# arduinoDcc1_2.net
KiCad netlist of a schematic drawn in EAGLE
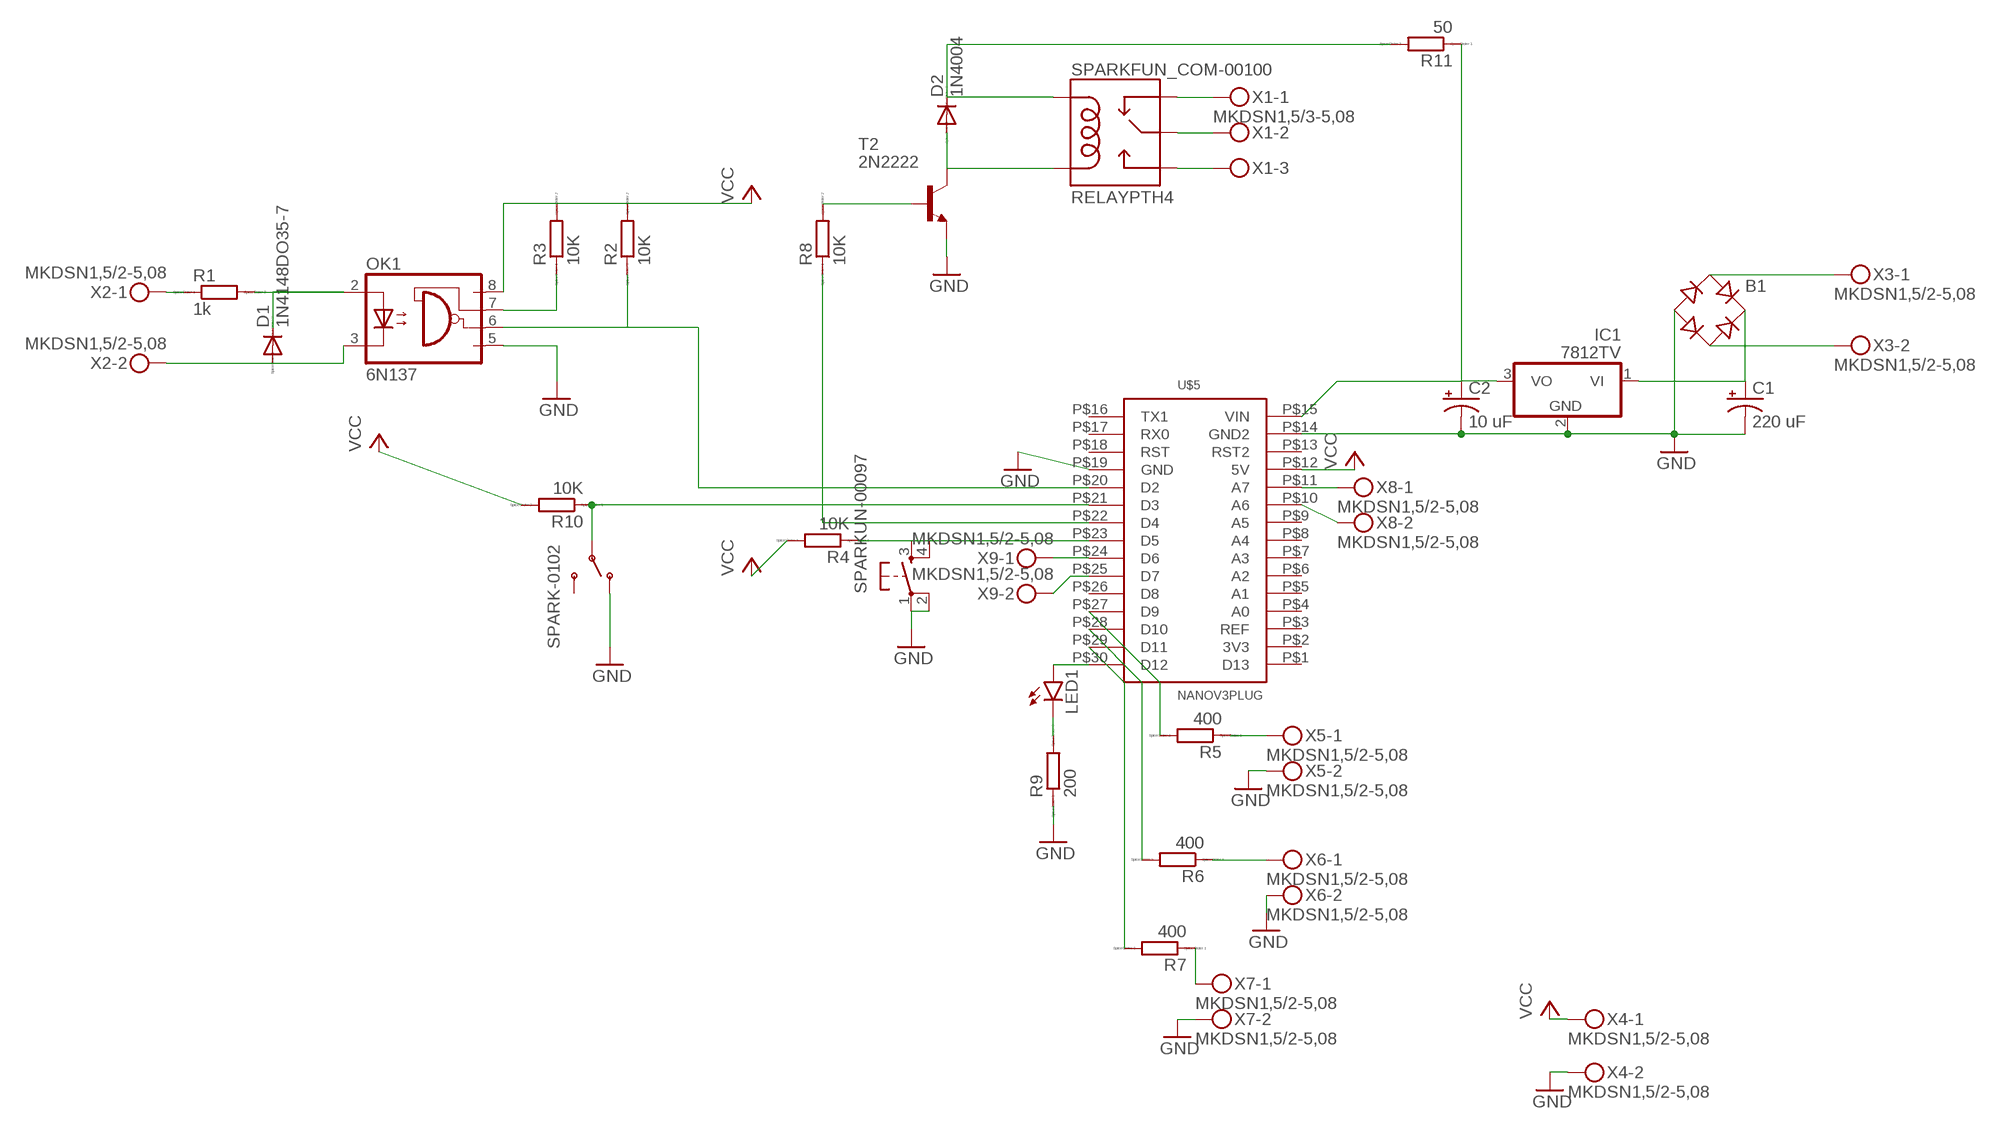
[diagram p0: schematic, sheet 1]

(export (version "E")
  (design (tool "Eeschema 10.0.6"))
  (components
    (comp (ref "B1")
      (value "RB1A")
      (footprint "eagle-import:RB1A")
      (libsource (lib "eagle-import") (part "RB1A"))
    )
    (comp (ref "C1")
      (value "220 uF")
      (footprint "eagle-import:CPOL-RADIAL-100UF-25V")
      (libsource (lib "eagle-import") (part "CAP_POLPTH1"))
    )
    (comp (ref "C2")
      (value "10 uF")
      (footprint "eagle-import:CPOL-RADIAL-100UF-25V")
      (libsource (lib "eagle-import") (part "CAP_POLPTH1"))
    )
    (comp (ref "D1")
      (value "1N4148DO35-7")
      (footprint "eagle-import:DO35-7")
      (libsource (lib "eagle-import") (part "1N4148DO35-7"))
    )
    (comp (ref "D2")
      (value "1N4004")
      (footprint "eagle-import:DO41-10")
      (libsource (lib "eagle-import") (part "1N4004"))
    )
    (comp (ref "IC1")
      (value "7812TV")
      (footprint "eagle-import:TO220V")
      (libsource (lib "eagle-import") (part "78TV12"))
    )
    (comp (ref "LED1")
      (value "LED3MM")
      (footprint "eagle-import:LED3MM")
      (libsource (lib "eagle-import") (part "LED3MM"))
    )
    (comp (ref "OK1")
      (value "6N137")
      (footprint "eagle-import:DIL08")
      (libsource (lib "eagle-import") (part "6N137"))
    )
    (comp (ref "R1")
      (value "1k")
      (footprint "eagle-import:0207_10")
      (libsource (lib "eagle-import") (part "R0207/10"))
    )
    (comp (ref "R2")
      (value "10K")
      (footprint "eagle-import:0207_10")
      (libsource (lib "eagle-import") (part "R0207/10"))
    )
    (comp (ref "R3")
      (value "10K")
      (footprint "eagle-import:0207_10")
      (libsource (lib "eagle-import") (part "R0207/10"))
    )
    (comp (ref "R4")
      (value "10K")
      (footprint "eagle-import:0207_10")
      (libsource (lib "eagle-import") (part "R0207/10"))
    )
    (comp (ref "R5")
      (value "400")
      (footprint "eagle-import:0207_10")
      (libsource (lib "eagle-import") (part "R0207/10"))
    )
    (comp (ref "R6")
      (value "400")
      (footprint "eagle-import:0207_10")
      (libsource (lib "eagle-import") (part "R0207/10"))
    )
    (comp (ref "R7")
      (value "400")
      (footprint "eagle-import:0207_10")
      (libsource (lib "eagle-import") (part "R0207/10"))
    )
    (comp (ref "R8")
      (value "10K")
      (footprint "eagle-import:0207_10")
      (libsource (lib "eagle-import") (part "R0207/10"))
    )
    (comp (ref "R9")
      (value "200")
      (footprint "eagle-import:0204_7")
      (libsource (lib "eagle-import") (part "R0204/7"))
    )
    (comp (ref "R10")
      (value "10K")
      (footprint "eagle-import:0207_10")
      (libsource (lib "eagle-import") (part "R0207/10"))
    )
    (comp (ref "R11")
      (value "50")
      (footprint "eagle-import:0207_10")
      (libsource (lib "eagle-import") (part "R0207/10"))
    )
    (comp (ref "SPARK-0102")
      (value "SWITCH-SPDTPTH")
      (footprint "eagle-import:SWITCH-SPDT")
      (libsource (lib "eagle-import") (part "SWITCH-SPDTPTH"))
    )
    (comp (ref "SPARKFUN_COM-00100")
      (value "RELAYPTH4")
      (footprint "eagle-import:RELAY-JZC")
      (libsource (lib "eagle-import") (part "RELAYPTH4"))
    )
    (comp (ref "SPARKUN-00097")
      (value "TAC_SWITCHPTH")
      (footprint "eagle-import:TACTILE-PTH")
      (libsource (lib "eagle-import") (part "TAC_SWITCHPTH"))
    )
    (comp (ref "T2")
      (value "2N2222")
      (footprint "eagle-import:TO18")
      (libsource (lib "eagle-import") (part "2N2222"))
    )
    (comp (ref "U$5")
      (value "NANOV3PLUG")
      (footprint "eagle-import:HEADER15-2")
      (libsource (lib "eagle-import") (part "NANOV3PLUG"))
    )
    (comp (ref "X1")
      (value "MKDSN1,5/3-5,08")
      (footprint "eagle-import:MKDSN1,5_3-5,08")
      (libsource (lib "eagle-import") (part "MKDSN1,5/3-5,08"))
    )
    (comp (ref "X2")
      (value "MKDSN1,5/2-5,08")
      (footprint "eagle-import:MKDSN1,5_2-5,08")
      (libsource (lib "eagle-import") (part "MKDSN1,5/2-5,08"))
    )
    (comp (ref "X3")
      (value "MKDSN1,5/2-5,08")
      (footprint "eagle-import:MKDSN1,5_2-5,08")
      (libsource (lib "eagle-import") (part "MKDSN1,5/2-5,08"))
    )
    (comp (ref "X4")
      (value "MKDSN1,5/2-5,08")
      (footprint "eagle-import:MKDSN1,5_2-5,08")
      (libsource (lib "eagle-import") (part "MKDSN1,5/2-5,08"))
    )
    (comp (ref "X5")
      (value "MKDSN1,5/2-5,08")
      (footprint "eagle-import:MKDSN1,5_2-5,08")
      (libsource (lib "eagle-import") (part "MKDSN1,5/2-5,08"))
    )
    (comp (ref "X6")
      (value "MKDSN1,5/2-5,08")
      (footprint "eagle-import:MKDSN1,5_2-5,08")
      (libsource (lib "eagle-import") (part "MKDSN1,5/2-5,08"))
    )
    (comp (ref "X7")
      (value "MKDSN1,5/2-5,08")
      (footprint "eagle-import:MKDSN1,5_2-5,08")
      (libsource (lib "eagle-import") (part "MKDSN1,5/2-5,08"))
    )
    (comp (ref "X8")
      (value "MKDSN1,5/2-5,08")
      (footprint "eagle-import:MKDSN1,5_2-5,08")
      (libsource (lib "eagle-import") (part "MKDSN1,5/2-5,08"))
    )
    (comp (ref "X9")
      (value "MKDSN1,5/2-5,08")
      (footprint "eagle-import:MKDSN1,5_2-5,08")
      (libsource (lib "eagle-import") (part "MKDSN1,5/2-5,08"))
    )
  )
  (nets
    (net (code "1") (name "GND") (class "Default")
      (node (ref "B1") (pin "-") (pinfunction "-_-") (pintype "passive"))
      (node (ref "C1") (pin "2") (pinfunction "-_2") (pintype "passive"))
      (node (ref "C2") (pin "2") (pinfunction "-_2") (pintype "passive"))
      (node (ref "IC1") (pin "2") (pinfunction "GND_2") (pintype "passive"))
      (node (ref "OK1") (pin "5") (pinfunction "GND_5") (pintype "passive"))
      (node (ref "R9") (pin "1") (pinfunction "1_1") (pintype "passive"))
      (node (ref "SPARK-0102") (pin "1") (pinfunction "O_1") (pintype "passive"))
      (node (ref "SPARKUN-00097") (pin "1") (pinfunction "1_1") (pintype "passive"))
      (node (ref "SPARKUN-00097") (pin "2") (pinfunction "2_2") (pintype "passive"))
      (node (ref "T2") (pin "1") (pinfunction "E_1") (pintype "passive"))
      (node (ref "U$5") (pin "P$14") (pinfunction "GND2_P$14") (pintype "bidirectional"))
      (node (ref "U$5") (pin "P$19") (pinfunction "GND_P$19") (pintype "bidirectional"))
      (node (ref "X4") (pin "2") (pinfunction "KL_2") (pintype "passive"))
      (node (ref "X5") (pin "2") (pinfunction "KL_2") (pintype "passive"))
      (node (ref "X6") (pin "2") (pinfunction "KL_2") (pintype "passive"))
      (node (ref "X7") (pin "2") (pinfunction "KL_2") (pintype "passive"))
    )
    (net (code "2") (name "Net-(C1-+)") (class "Default")
      (node (ref "B1") (pin "+") (pinfunction "+_+") (pintype "passive"))
      (node (ref "C1") (pin "1") (pinfunction "+_1") (pintype "passive"))
      (node (ref "IC1") (pin "1") (pinfunction "VI_1") (pintype "input"))
    )
    (net (code "3") (name "Net-(C2-+)") (class "Default")
      (node (ref "C2") (pin "1") (pinfunction "+_1") (pintype "passive"))
      (node (ref "IC1") (pin "3") (pinfunction "VO_3") (pintype "passive"))
      (node (ref "R11") (pin "1") (pinfunction "1_1") (pintype "passive"))
      (node (ref "U$5") (pin "P$15") (pinfunction "VIN_P$15") (pintype "bidirectional"))
    )
    (net (code "4") (name "Net-(LED1-C)") (class "Default")
      (node (ref "LED1") (pin "K") (pinfunction "C_K") (pintype "passive"))
      (node (ref "R9") (pin "2") (pinfunction "2_2") (pintype "passive"))
    )
    (net (code "5") (name "Net-(OK1-A)") (class "Default")
      (node (ref "D1") (pin "C") (pinfunction "C_C") (pintype "passive"))
      (node (ref "OK1") (pin "2") (pinfunction "A_2") (pintype "passive"))
      (node (ref "R1") (pin "2") (pinfunction "2_2") (pintype "passive"))
    )
    (net (code "6") (name "Net-(OK1-C)") (class "Default")
      (node (ref "D1") (pin "A") (pinfunction "A_A") (pintype "passive"))
      (node (ref "OK1") (pin "3") (pinfunction "C_3") (pintype "passive"))
      (node (ref "X2") (pin "2") (pinfunction "KL_2") (pintype "passive"))
    )
    (net (code "7") (name "Net-(OK1-VE)") (class "Default")
      (node (ref "OK1") (pin "7") (pinfunction "VE_7") (pintype "passive"))
      (node (ref "R3") (pin "1") (pinfunction "1_1") (pintype "passive"))
    )
    (net (code "8") (name "Net-(OK1-VO)") (class "Default")
      (node (ref "OK1") (pin "6") (pinfunction "VO_6") (pintype "passive"))
      (node (ref "R2") (pin "1") (pinfunction "1_1") (pintype "passive"))
      (node (ref "U$5") (pin "P$20") (pinfunction "D2_P$20") (pintype "bidirectional"))
    )
    (net (code "9") (name "Net-(SPARK-0102-P)") (class "Default")
      (node (ref "R10") (pin "1") (pinfunction "1_1") (pintype "passive"))
      (node (ref "SPARK-0102") (pin "2") (pinfunction "P_2") (pintype "passive"))
      (node (ref "U$5") (pin "P$21") (pinfunction "D3_P$21") (pintype "bidirectional"))
    )
    (net (code "10") (name "Net-(SPARKFUN_COM-00100-COIL1)") (class "Default")
      (node (ref "D2") (pin "C") (pinfunction "C_C") (pintype "passive"))
      (node (ref "R11") (pin "2") (pinfunction "2_2") (pintype "passive"))
      (node (ref "SPARKFUN_COM-00100") (pin "5") (pinfunction "COIL1_5") (pintype "bidirectional"))
    )
    (net (code "11") (name "Net-(SPARKFUN_COM-00100-COIL2)") (class "Default")
      (node (ref "D2") (pin "A") (pinfunction "A_A") (pintype "passive"))
      (node (ref "SPARKFUN_COM-00100") (pin "1") (pinfunction "COIL2_1") (pintype "bidirectional"))
      (node (ref "T2") (pin "3") (pinfunction "C_3") (pintype "passive"))
    )
    (net (code "12") (name "Net-(SPARKFUN_COM-00100-MAIN)") (class "Default")
      (node (ref "SPARKFUN_COM-00100") (pin "4") (pinfunction "MAIN_4") (pintype "bidirectional"))
      (node (ref "X1") (pin "2") (pinfunction "KL_2") (pintype "passive"))
    )
    (net (code "13") (name "Net-(SPARKFUN_COM-00100-NC)") (class "Default")
      (node (ref "SPARKFUN_COM-00100") (pin "2") (pinfunction "NC_2") (pintype "bidirectional"))
      (node (ref "X1") (pin "1") (pinfunction "KL_1") (pintype "passive"))
    )
    (net (code "14") (name "Net-(SPARKFUN_COM-00100-NO)") (class "Default")
      (node (ref "SPARKFUN_COM-00100") (pin "3") (pinfunction "NO_3") (pintype "bidirectional"))
      (node (ref "X1") (pin "3") (pinfunction "KL_3") (pintype "passive"))
    )
    (net (code "15") (name "Net-(T2-B)") (class "Default")
      (node (ref "R8") (pin "2") (pinfunction "2_2") (pintype "passive"))
      (node (ref "T2") (pin "2") (pinfunction "B_2") (pintype "passive"))
    )
    (net (code "16") (name "Net-(U$5-A6)") (class "Default")
      (node (ref "U$5") (pin "P$10") (pinfunction "A6_P$10") (pintype "bidirectional"))
      (node (ref "X8") (pin "2") (pinfunction "KL_2") (pintype "passive"))
    )
    (net (code "17") (name "Net-(U$5-A7)") (class "Default")
      (node (ref "U$5") (pin "P$11") (pinfunction "A7_P$11") (pintype "bidirectional"))
      (node (ref "X8") (pin "1") (pinfunction "KL_1") (pintype "passive"))
    )
    (net (code "18") (name "Net-(U$5-D4)") (class "Default")
      (node (ref "R8") (pin "1") (pinfunction "1_1") (pintype "passive"))
      (node (ref "U$5") (pin "P$22") (pinfunction "D4_P$22") (pintype "bidirectional"))
    )
    (net (code "19") (name "Net-(U$5-D5)") (class "Default")
      (node (ref "R4") (pin "1") (pinfunction "1_1") (pintype "passive"))
      (node (ref "SPARKUN-00097") (pin "3") (pinfunction "3_3") (pintype "passive"))
      (node (ref "SPARKUN-00097") (pin "4") (pinfunction "4_4") (pintype "passive"))
      (node (ref "U$5") (pin "P$23") (pinfunction "D5_P$23") (pintype "bidirectional"))
    )
    (net (code "20") (name "Net-(U$5-D6)") (class "Default")
      (node (ref "U$5") (pin "P$24") (pinfunction "D6_P$24") (pintype "bidirectional"))
      (node (ref "X9") (pin "1") (pinfunction "KL_1") (pintype "passive"))
    )
    (net (code "21") (name "Net-(U$5-D7)") (class "Default")
      (node (ref "U$5") (pin "P$25") (pinfunction "D7_P$25") (pintype "bidirectional"))
      (node (ref "X9") (pin "2") (pinfunction "KL_2") (pintype "passive"))
    )
    (net (code "22") (name "Net-(U$5-D9)") (class "Default")
      (node (ref "R5") (pin "2") (pinfunction "2_2") (pintype "passive"))
      (node (ref "U$5") (pin "P$27") (pinfunction "D9_P$27") (pintype "bidirectional"))
    )
    (net (code "23") (name "Net-(U$5-D10)") (class "Default")
      (node (ref "R6") (pin "2") (pinfunction "2_2") (pintype "passive"))
      (node (ref "U$5") (pin "P$28") (pinfunction "D10_P$28") (pintype "bidirectional"))
    )
    (net (code "24") (name "Net-(U$5-D11)") (class "Default")
      (node (ref "R7") (pin "2") (pinfunction "2_2") (pintype "passive"))
      (node (ref "U$5") (pin "P$29") (pinfunction "D11_P$29") (pintype "bidirectional"))
    )
    (net (code "25") (name "Net-(U$5-D12)") (class "Default")
      (node (ref "LED1") (pin "A") (pinfunction "A_A") (pintype "passive"))
      (node (ref "U$5") (pin "P$30") (pinfunction "D12_P$30") (pintype "bidirectional"))
    )
    (net (code "26") (name "Net-(X2A-KL)") (class "Default")
      (node (ref "R1") (pin "1") (pinfunction "1_1") (pintype "passive"))
      (node (ref "X2") (pin "1") (pinfunction "KL_1") (pintype "passive"))
    )
    (net (code "27") (name "Net-(X3A-KL)") (class "Default")
      (node (ref "B1") (pin "AC1") (pinfunction "AC1_AC1") (pintype "passive"))
      (node (ref "X3") (pin "1") (pinfunction "KL_1") (pintype "passive"))
    )
    (net (code "28") (name "Net-(X3B-KL)") (class "Default")
      (node (ref "B1") (pin "AC2") (pinfunction "AC2_AC2") (pintype "passive"))
      (node (ref "X3") (pin "2") (pinfunction "KL_2") (pintype "passive"))
    )
    (net (code "29") (name "Net-(X5A-KL)") (class "Default")
      (node (ref "R5") (pin "1") (pinfunction "1_1") (pintype "passive"))
      (node (ref "X5") (pin "1") (pinfunction "KL_1") (pintype "passive"))
    )
    (net (code "30") (name "Net-(X6A-KL)") (class "Default")
      (node (ref "R6") (pin "1") (pinfunction "1_1") (pintype "passive"))
      (node (ref "X6") (pin "1") (pinfunction "KL_1") (pintype "passive"))
    )
    (net (code "31") (name "Net-(X7A-KL)") (class "Default")
      (node (ref "R7") (pin "1") (pinfunction "1_1") (pintype "passive"))
      (node (ref "X7") (pin "1") (pinfunction "KL_1") (pintype "passive"))
    )
    (net (code "32") (name "VCC") (class "Default")
      (node (ref "OK1") (pin "8") (pinfunction "VCC_8") (pintype "passive"))
      (node (ref "R10") (pin "2") (pinfunction "2_2") (pintype "passive"))
      (node (ref "R2") (pin "2") (pinfunction "2_2") (pintype "passive"))
      (node (ref "R3") (pin "2") (pinfunction "2_2") (pintype "passive"))
      (node (ref "R4") (pin "2") (pinfunction "2_2") (pintype "passive"))
      (node (ref "U$5") (pin "P$12") (pinfunction "5V_P$12") (pintype "bidirectional"))
      (node (ref "X4") (pin "1") (pinfunction "KL_1") (pintype "passive"))
    )
    (net (code "33") (name "unconnected-(SPARK-0102-S-Pad3)") (class "Default")
      (node (ref "SPARK-0102") (pin "3") (pinfunction "S_3") (pintype "passive"))
    )
    (net (code "34") (name "unconnected-(U$5-3V3-PadP$2)") (class "Default")
      (node (ref "U$5") (pin "P$2") (pinfunction "3V3_P$2") (pintype "bidirectional"))
    )
    (net (code "35") (name "unconnected-(U$5-A0-PadP$4)") (class "Default")
      (node (ref "U$5") (pin "P$4") (pinfunction "A0_P$4") (pintype "bidirectional"))
    )
    (net (code "36") (name "unconnected-(U$5-A1-PadP$5)") (class "Default")
      (node (ref "U$5") (pin "P$5") (pinfunction "A1_P$5") (pintype "bidirectional"))
    )
    (net (code "37") (name "unconnected-(U$5-A2-PadP$6)") (class "Default")
      (node (ref "U$5") (pin "P$6") (pinfunction "A2_P$6") (pintype "bidirectional"))
    )
    (net (code "38") (name "unconnected-(U$5-A3-PadP$7)") (class "Default")
      (node (ref "U$5") (pin "P$7") (pinfunction "A3_P$7") (pintype "bidirectional"))
    )
    (net (code "39") (name "unconnected-(U$5-A4-PadP$8)") (class "Default")
      (node (ref "U$5") (pin "P$8") (pinfunction "A4_P$8") (pintype "bidirectional"))
    )
    (net (code "40") (name "unconnected-(U$5-A5-PadP$9)") (class "Default")
      (node (ref "U$5") (pin "P$9") (pinfunction "A5_P$9") (pintype "bidirectional"))
    )
    (net (code "41") (name "unconnected-(U$5-D8-PadP$26)") (class "Default")
      (node (ref "U$5") (pin "P$26") (pinfunction "D8_P$26") (pintype "bidirectional"))
    )
    (net (code "42") (name "unconnected-(U$5-D13-PadP$1)") (class "Default")
      (node (ref "U$5") (pin "P$1") (pinfunction "D13_P$1") (pintype "bidirectional"))
    )
    (net (code "43") (name "unconnected-(U$5-REF-PadP$3)") (class "Default")
      (node (ref "U$5") (pin "P$3") (pinfunction "REF_P$3") (pintype "bidirectional"))
    )
    (net (code "44") (name "unconnected-(U$5-RST-PadP$18)") (class "Default")
      (node (ref "U$5") (pin "P$18") (pinfunction "RST_P$18") (pintype "bidirectional"))
    )
    (net (code "45") (name "unconnected-(U$5-RST2-PadP$13)") (class "Default")
      (node (ref "U$5") (pin "P$13") (pinfunction "RST2_P$13") (pintype "bidirectional"))
    )
    (net (code "46") (name "unconnected-(U$5-RX0-PadP$17)") (class "Default")
      (node (ref "U$5") (pin "P$17") (pinfunction "RX0_P$17") (pintype "bidirectional"))
    )
    (net (code "47") (name "unconnected-(U$5-TX1-PadP$16)") (class "Default")
      (node (ref "U$5") (pin "P$16") (pinfunction "TX1_P$16") (pintype "bidirectional"))
    )
  )
)
